# MCU_STM32F103RCT6.net
KiCad netlist of a schematic drawn in Altium Designer
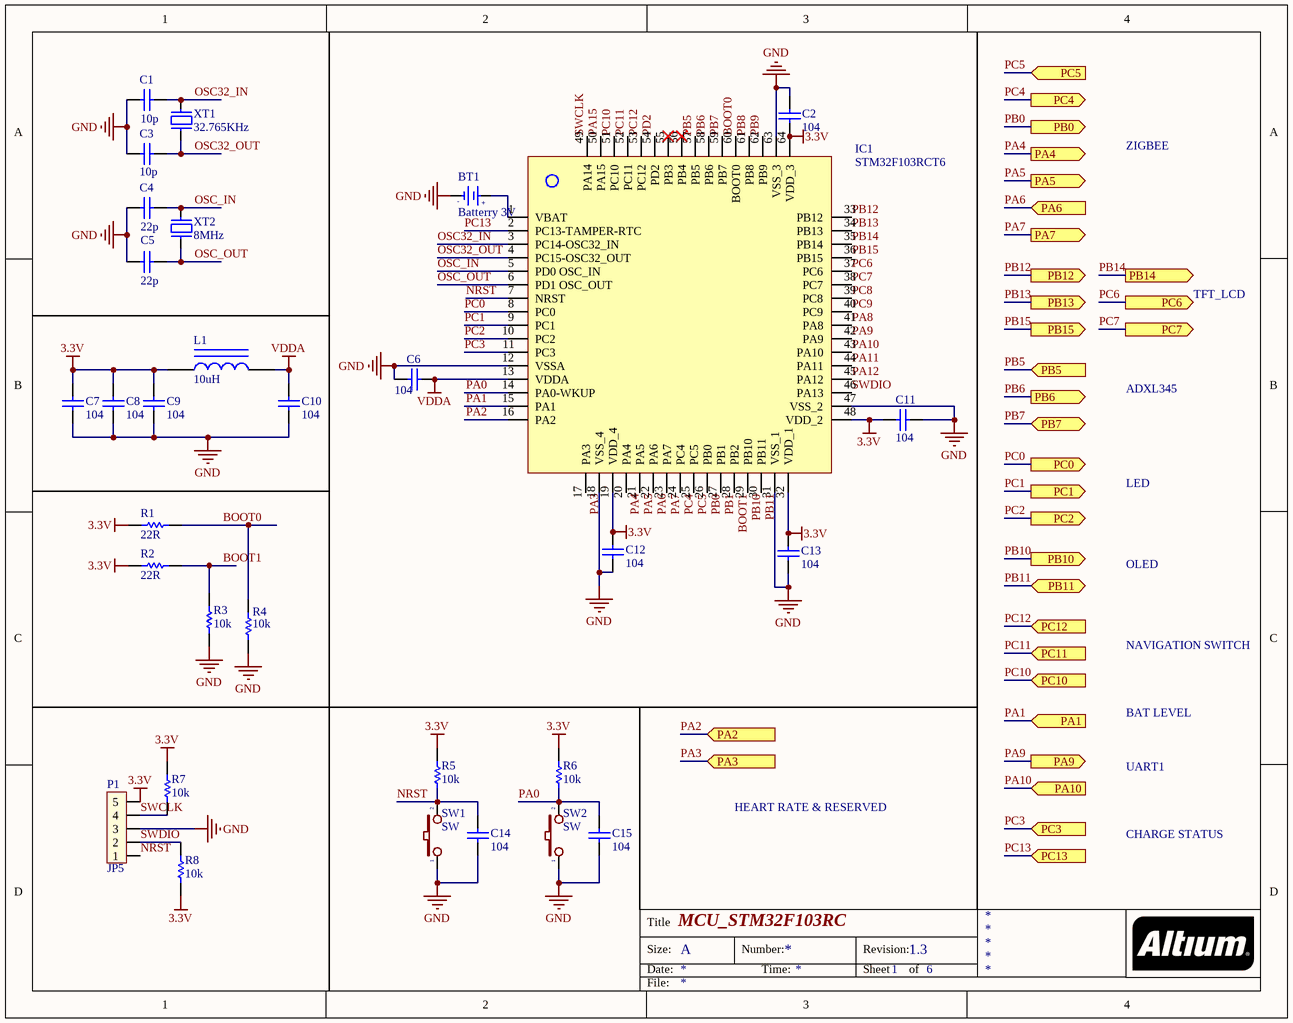
[diagram p0: MCU_STM32F103RCT6.SchDoc]

(export (version "E")
  (design (tool "Eeschema 10.0.6"))
  (components
    (comp (ref "BT1")
      (value "Batterry 3V")
      (footprint "Battery3V_SMD")
      (libsource (lib "HoangViet_AltiumLib") (part "Battery3V"))
    )
    (comp (ref "C1")
      (value "10p")
      (footprint "Cap 0805")
      (libsource (lib "HoangViet_AltiumLib") (part "Cap_0805"))
    )
    (comp (ref "C2")
      (value "104")
      (footprint "Cap 0805")
      (libsource (lib "HoangViet_AltiumLib") (part "Cap_0805"))
    )
    (comp (ref "C3")
      (value "10p")
      (footprint "Cap 0805")
      (libsource (lib "HoangViet_AltiumLib") (part "Cap_0805"))
    )
    (comp (ref "C4")
      (value "22p")
      (footprint "Cap 0805")
      (libsource (lib "HoangViet_AltiumLib") (part "Cap_0805"))
    )
    (comp (ref "C5")
      (value "22p")
      (footprint "Cap 0805")
      (libsource (lib "HoangViet_AltiumLib") (part "Cap_0805"))
    )
    (comp (ref "C6")
      (value "104")
      (footprint "Cap 0805")
      (libsource (lib "HoangViet_AltiumLib") (part "Cap_0805"))
    )
    (comp (ref "C7")
      (value "104")
      (footprint "Cap 0805")
      (libsource (lib "HoangViet_AltiumLib") (part "Cap_0805"))
    )
    (comp (ref "C8")
      (value "104")
      (footprint "Cap 0805")
      (libsource (lib "HoangViet_AltiumLib") (part "Cap_0805"))
    )
    (comp (ref "C9")
      (value "104")
      (footprint "Cap 0805")
      (libsource (lib "HoangViet_AltiumLib") (part "Cap_0805"))
    )
    (comp (ref "C10")
      (value "104")
      (footprint "Cap 0805")
      (libsource (lib "HoangViet_AltiumLib") (part "Cap_0805"))
    )
    (comp (ref "C11")
      (value "104")
      (footprint "Cap 0805")
      (libsource (lib "HoangViet_AltiumLib") (part "Cap_0805"))
    )
    (comp (ref "C12")
      (value "104")
      (footprint "Cap 0805")
      (libsource (lib "HoangViet_AltiumLib") (part "Cap_0805"))
    )
    (comp (ref "C13")
      (value "104")
      (footprint "Cap 0805")
      (libsource (lib "HoangViet_AltiumLib") (part "Cap_0805"))
    )
    (comp (ref "C14")
      (value "104")
      (footprint "Cap 0805")
      (libsource (lib "HoangViet_AltiumLib") (part "Cap_0805"))
    )
    (comp (ref "C15")
      (value "104")
      (footprint "Cap 0805")
      (libsource (lib "HoangViet_AltiumLib") (part "Cap_0805"))
    )
    (comp (ref "IC1")
      (value "STM32F103RCT6")
      (footprint "stm32f103rct6")
      (libsource (lib "linhien69") (part "stm32f103rct6"))
    )
    (comp (ref "L1")
      (value "10uH")
      (footprint "Inductor 0805")
      (description "inductor 0805")
      (libsource (lib "HoangViet_AltiumLib") (part "inductor_0805"))
    )
    (comp (ref "P1") (value "JP5") (footprint "JP5") (libsource (lib "linhien69") (part "JP5")))
    (comp (ref "R1")
      (value "22R")
      (footprint "RES 0805")
      (description "resistor smd0805")
      (libsource (lib "HoangViet_AltiumLib") (part "Res_0805"))
    )
    (comp (ref "R2")
      (value "22R")
      (footprint "RES 0805")
      (description "resistor smd0805")
      (libsource (lib "HoangViet_AltiumLib") (part "Res_0805"))
    )
    (comp (ref "R3")
      (value "10k")
      (footprint "RES 0805")
      (description "resistor smd0805")
      (libsource (lib "HoangViet_AltiumLib") (part "Res_0805"))
    )
    (comp (ref "R4")
      (value "10k")
      (footprint "RES 0805")
      (description "resistor smd0805")
      (libsource (lib "HoangViet_AltiumLib") (part "Res_0805"))
    )
    (comp (ref "R5")
      (value "10k")
      (footprint "RES 0805")
      (description "resistor smd0805")
      (libsource (lib "HoangViet_AltiumLib") (part "Res_0805"))
    )
    (comp (ref "R6")
      (value "10k")
      (footprint "RES 0805")
      (description "resistor smd0805")
      (libsource (lib "HoangViet_AltiumLib") (part "Res_0805"))
    )
    (comp (ref "R7")
      (value "10k")
      (footprint "RES 0805")
      (description "resistor smd0805")
      (libsource (lib "HoangViet_AltiumLib") (part "Res_0805"))
    )
    (comp (ref "R8")
      (value "10k")
      (footprint "RES 0805")
      (description "resistor smd0805")
      (libsource (lib "HoangViet_AltiumLib") (part "Res_0805"))
    )
    (comp (ref "SW1")
      (value "SW")
      (footprint "sw_ran_2pin")
      (description "Switch button 2 pin")
      (libsource (lib "linhien69") (part "SW2"))
    )
    (comp (ref "SW2")
      (value "SW")
      (footprint "sw_ran_2pin")
      (description "Switch button 2 pin")
      (libsource (lib "linhien69") (part "SW2"))
    )
    (comp (ref "XT1")
      (value "32.765KHz")
      (footprint "XTAL_32K")
      (description "Xtal")
      (libsource (lib "HoangViet_AltiumLib") (part "Xtal"))
    )
    (comp (ref "XT2")
      (value "8MHz")
      (footprint "XTAL_6035")
      (description "Xtal")
      (libsource (lib "HoangViet_AltiumLib") (part "Xtal"))
    )
  )
  (nets
    (net (code "1") (name "/BOOT0") (class "Default")
      (node (ref "IC1") (pin "60") (pinfunction "BOOT0_60") (pintype "passive"))
      (node (ref "R1") (pin "1") (pinfunction "1_1") (pintype "passive"))
      (node (ref "R4") (pin "2") (pinfunction "2_2") (pintype "passive"))
    )
    (net (code "2") (name "/BOOT1") (class "Default")
      (node (ref "IC1") (pin "28") (pinfunction "PB2_28") (pintype "passive"))
      (node (ref "R2") (pin "1") (pinfunction "1_1") (pintype "passive"))
      (node (ref "R3") (pin "2") (pinfunction "2_2") (pintype "passive"))
    )
    (net (code "3") (name "/NRST") (class "Default")
      (node (ref "C14") (pin "2") (pinfunction "2_2") (pintype "passive"))
      (node (ref "IC1") (pin "7") (pinfunction "NRST_7") (pintype "passive"))
      (node (ref "P1") (pin "1") (pinfunction "1_1") (pintype "passive"))
      (node (ref "R5") (pin "1") (pinfunction "1_1") (pintype "passive"))
      (node (ref "SW1") (pin "2") (pinfunction "2_2") (pintype "passive"))
    )
    (net (code "4") (name "/OSC32_IN") (class "Default")
      (node (ref "C1") (pin "1") (pinfunction "1_1") (pintype "passive"))
      (node (ref "IC1") (pin "3") (pinfunction "PC14-OSC32_IN_3") (pintype "passive"))
      (node (ref "XT1") (pin "2") (pinfunction "2_2") (pintype "passive"))
    )
    (net (code "5") (name "/OSC32_OUT") (class "Default")
      (node (ref "C3") (pin "1") (pinfunction "1_1") (pintype "passive"))
      (node (ref "IC1") (pin "4") (pinfunction "PC15-OSC32_OUT_4") (pintype "passive"))
      (node (ref "XT1") (pin "1") (pinfunction "1_1") (pintype "passive"))
    )
    (net (code "6") (name "/OSC_IN") (class "Default")
      (node (ref "C4") (pin "1") (pinfunction "1_1") (pintype "passive"))
      (node (ref "IC1") (pin "5") (pinfunction "PD0_OSC_IN_5") (pintype "passive"))
      (node (ref "XT2") (pin "2") (pinfunction "2_2") (pintype "passive"))
    )
    (net (code "7") (name "/OSC_OUT") (class "Default")
      (node (ref "C5") (pin "1") (pinfunction "1_1") (pintype "passive"))
      (node (ref "IC1") (pin "6") (pinfunction "PD1_OSC_OUT_6") (pintype "passive"))
      (node (ref "XT2") (pin "1") (pinfunction "1_1") (pintype "passive"))
    )
    (net (code "8") (name "/PA0") (class "Default")
      (node (ref "C15") (pin "2") (pinfunction "2_2") (pintype "passive"))
      (node (ref "IC1") (pin "14") (pinfunction "PA0-WKUP_14") (pintype "passive"))
      (node (ref "R6") (pin "1") (pinfunction "1_1") (pintype "passive"))
      (node (ref "SW2") (pin "2") (pinfunction "2_2") (pintype "passive"))
    )
    (net (code "9") (name "/PA1") (class "Default")
      (node (ref "IC1") (pin "15") (pinfunction "PA1_15") (pintype "passive"))
    )
    (net (code "10") (name "/PA2") (class "Default")
      (node (ref "IC1") (pin "16") (pinfunction "PA2_16") (pintype "passive"))
    )
    (net (code "11") (name "/PA3") (class "Default")
      (node (ref "IC1") (pin "17") (pinfunction "PA3_17") (pintype "passive"))
    )
    (net (code "12") (name "/PA4") (class "Default")
      (node (ref "IC1") (pin "20") (pinfunction "PA4_20") (pintype "passive"))
    )
    (net (code "13") (name "/PA5") (class "Default")
      (node (ref "IC1") (pin "21") (pinfunction "PA5_21") (pintype "passive"))
    )
    (net (code "14") (name "/PA6") (class "Default")
      (node (ref "IC1") (pin "22") (pinfunction "PA6_22") (pintype "passive"))
    )
    (net (code "15") (name "/PA7") (class "Default")
      (node (ref "IC1") (pin "23") (pinfunction "PA7_23") (pintype "passive"))
    )
    (net (code "16") (name "/PA8") (class "Default")
      (node (ref "IC1") (pin "41") (pinfunction "PA8_41") (pintype "passive"))
    )
    (net (code "17") (name "/PA9") (class "Default")
      (node (ref "IC1") (pin "42") (pinfunction "PA9_42") (pintype "passive"))
    )
    (net (code "18") (name "/PA10") (class "Default")
      (node (ref "IC1") (pin "43") (pinfunction "PA10_43") (pintype "passive"))
    )
    (net (code "19") (name "/PA11") (class "Default")
      (node (ref "IC1") (pin "44") (pinfunction "PA11_44") (pintype "passive"))
    )
    (net (code "20") (name "/PA12") (class "Default")
      (node (ref "IC1") (pin "45") (pinfunction "PA12_45") (pintype "passive"))
    )
    (net (code "21") (name "/PA15") (class "Default")
      (node (ref "IC1") (pin "50") (pinfunction "PA15_50") (pintype "passive"))
    )
    (net (code "22") (name "/PB0") (class "Default")
      (node (ref "IC1") (pin "26") (pinfunction "PB0_26") (pintype "passive"))
    )
    (net (code "23") (name "/PB1") (class "Default")
      (node (ref "IC1") (pin "27") (pinfunction "PB1_27") (pintype "passive"))
    )
    (net (code "24") (name "/PB5") (class "Default")
      (node (ref "IC1") (pin "57") (pinfunction "PB5_57") (pintype "passive"))
    )
    (net (code "25") (name "/PB6") (class "Default")
      (node (ref "IC1") (pin "58") (pinfunction "PB6_58") (pintype "passive"))
    )
    (net (code "26") (name "/PB7") (class "Default")
      (node (ref "IC1") (pin "59") (pinfunction "PB7_59") (pintype "passive"))
    )
    (net (code "27") (name "/PB8") (class "Default")
      (node (ref "IC1") (pin "61") (pinfunction "PB8_61") (pintype "passive"))
    )
    (net (code "28") (name "/PB9") (class "Default")
      (node (ref "IC1") (pin "62") (pinfunction "PB9_62") (pintype "passive"))
    )
    (net (code "29") (name "/PB10") (class "Default")
      (node (ref "IC1") (pin "29") (pinfunction "PB10_29") (pintype "passive"))
    )
    (net (code "30") (name "/PB11") (class "Default")
      (node (ref "IC1") (pin "30") (pinfunction "PB11_30") (pintype "passive"))
    )
    (net (code "31") (name "/PB12") (class "Default")
      (node (ref "IC1") (pin "33") (pinfunction "PB12_33") (pintype "passive"))
    )
    (net (code "32") (name "/PB13") (class "Default")
      (node (ref "IC1") (pin "34") (pinfunction "PB13_34") (pintype "passive"))
    )
    (net (code "33") (name "/PB14") (class "Default")
      (node (ref "IC1") (pin "35") (pinfunction "PB14_35") (pintype "passive"))
    )
    (net (code "34") (name "/PB15") (class "Default")
      (node (ref "IC1") (pin "36") (pinfunction "PB15_36") (pintype "passive"))
    )
    (net (code "35") (name "/PC0") (class "Default")
      (node (ref "IC1") (pin "8") (pinfunction "PC0_8") (pintype "passive"))
    )
    (net (code "36") (name "/PC1") (class "Default")
      (node (ref "IC1") (pin "9") (pinfunction "PC1_9") (pintype "passive"))
    )
    (net (code "37") (name "/PC2") (class "Default")
      (node (ref "IC1") (pin "10") (pinfunction "PC2_10") (pintype "passive"))
    )
    (net (code "38") (name "/PC3") (class "Default")
      (node (ref "IC1") (pin "11") (pinfunction "PC3_11") (pintype "passive"))
    )
    (net (code "39") (name "/PC4") (class "Default")
      (node (ref "IC1") (pin "24") (pinfunction "PC4_24") (pintype "passive"))
    )
    (net (code "40") (name "/PC5") (class "Default")
      (node (ref "IC1") (pin "25") (pinfunction "PC5_25") (pintype "passive"))
    )
    (net (code "41") (name "/PC6") (class "Default")
      (node (ref "IC1") (pin "37") (pinfunction "PC6_37") (pintype "passive"))
    )
    (net (code "42") (name "/PC7") (class "Default")
      (node (ref "IC1") (pin "38") (pinfunction "PC7_38") (pintype "passive"))
    )
    (net (code "43") (name "/PC8") (class "Default")
      (node (ref "IC1") (pin "39") (pinfunction "PC8_39") (pintype "passive"))
    )
    (net (code "44") (name "/PC9") (class "Default")
      (node (ref "IC1") (pin "40") (pinfunction "PC9_40") (pintype "passive"))
    )
    (net (code "45") (name "/PC10") (class "Default")
      (node (ref "IC1") (pin "51") (pinfunction "PC10_51") (pintype "passive"))
    )
    (net (code "46") (name "/PC11") (class "Default")
      (node (ref "IC1") (pin "52") (pinfunction "PC11_52") (pintype "passive"))
    )
    (net (code "47") (name "/PC12") (class "Default")
      (node (ref "IC1") (pin "53") (pinfunction "PC12_53") (pintype "passive"))
    )
    (net (code "48") (name "/PC13") (class "Default")
      (node (ref "IC1") (pin "2") (pinfunction "PC13-TAMPER-RTC_2") (pintype "passive"))
    )
    (net (code "49") (name "/PD2") (class "Default")
      (node (ref "IC1") (pin "54") (pinfunction "PD2_54") (pintype "passive"))
    )
    (net (code "50") (name "/SWCLK") (class "Default")
      (node (ref "IC1") (pin "49") (pinfunction "PA14_49") (pintype "passive"))
      (node (ref "P1") (pin "4") (pinfunction "4_4") (pintype "passive"))
      (node (ref "R7") (pin "1") (pinfunction "1_1") (pintype "passive"))
    )
    (net (code "51") (name "/SWDIO") (class "Default")
      (node (ref "IC1") (pin "46") (pinfunction "PA13_46") (pintype "passive"))
      (node (ref "P1") (pin "2") (pinfunction "2_2") (pintype "passive"))
      (node (ref "R8") (pin "2") (pinfunction "2_2") (pintype "passive"))
    )
    (net (code "52") (name "3.3V") (class "Default")
      (node (ref "C11") (pin "2") (pinfunction "2_2") (pintype "passive"))
      (node (ref "C12") (pin "2") (pinfunction "2_2") (pintype "passive"))
      (node (ref "C13") (pin "2") (pinfunction "2_2") (pintype "passive"))
      (node (ref "C2") (pin "2") (pinfunction "2_2") (pintype "passive"))
      (node (ref "C7") (pin "2") (pinfunction "2_2") (pintype "passive"))
      (node (ref "C8") (pin "2") (pinfunction "2_2") (pintype "passive"))
      (node (ref "C9") (pin "2") (pinfunction "2_2") (pintype "passive"))
      (node (ref "IC1") (pin "19") (pinfunction "VDD_4_19") (pintype "passive"))
      (node (ref "IC1") (pin "32") (pinfunction "VDD_1_32") (pintype "passive"))
      (node (ref "IC1") (pin "48") (pinfunction "VDD_2_48") (pintype "passive"))
      (node (ref "IC1") (pin "64") (pinfunction "VDD_3_64") (pintype "passive"))
      (node (ref "L1") (pin "1") (pinfunction "1_1") (pintype "passive"))
      (node (ref "P1") (pin "5") (pinfunction "5_5") (pintype "passive"))
      (node (ref "R1") (pin "2") (pinfunction "2_2") (pintype "passive"))
      (node (ref "R2") (pin "2") (pinfunction "2_2") (pintype "passive"))
      (node (ref "R5") (pin "2") (pinfunction "2_2") (pintype "passive"))
      (node (ref "R6") (pin "2") (pinfunction "2_2") (pintype "passive"))
      (node (ref "R7") (pin "2") (pinfunction "2_2") (pintype "passive"))
      (node (ref "R8") (pin "1") (pinfunction "1_1") (pintype "passive"))
    )
    (net (code "53") (name "GND") (class "Default")
      (node (ref "BT1") (pin "2") (pinfunction "GND_2") (pintype "passive"))
      (node (ref "C1") (pin "2") (pinfunction "2_2") (pintype "passive"))
      (node (ref "C10") (pin "1") (pinfunction "1_1") (pintype "passive"))
      (node (ref "C11") (pin "1") (pinfunction "1_1") (pintype "passive"))
      (node (ref "C12") (pin "1") (pinfunction "1_1") (pintype "passive"))
      (node (ref "C13") (pin "1") (pinfunction "1_1") (pintype "passive"))
      (node (ref "C14") (pin "1") (pinfunction "1_1") (pintype "passive"))
      (node (ref "C15") (pin "1") (pinfunction "1_1") (pintype "passive"))
      (node (ref "C2") (pin "1") (pinfunction "1_1") (pintype "passive"))
      (node (ref "C3") (pin "2") (pinfunction "2_2") (pintype "passive"))
      (node (ref "C4") (pin "2") (pinfunction "2_2") (pintype "passive"))
      (node (ref "C5") (pin "2") (pinfunction "2_2") (pintype "passive"))
      (node (ref "C6") (pin "2") (pinfunction "2_2") (pintype "passive"))
      (node (ref "C7") (pin "1") (pinfunction "1_1") (pintype "passive"))
      (node (ref "C8") (pin "1") (pinfunction "1_1") (pintype "passive"))
      (node (ref "C9") (pin "1") (pinfunction "1_1") (pintype "passive"))
      (node (ref "IC1") (pin "12") (pinfunction "VSSA_12") (pintype "passive"))
      (node (ref "IC1") (pin "18") (pinfunction "VSS_4_18") (pintype "passive"))
      (node (ref "IC1") (pin "31") (pinfunction "VSS_1_31") (pintype "passive"))
      (node (ref "IC1") (pin "47") (pinfunction "VSS_2_47") (pintype "passive"))
      (node (ref "IC1") (pin "63") (pinfunction "VSS_3_63") (pintype "passive"))
      (node (ref "P1") (pin "3") (pinfunction "3_3") (pintype "passive"))
      (node (ref "R3") (pin "1") (pinfunction "1_1") (pintype "passive"))
      (node (ref "R4") (pin "1") (pinfunction "1_1") (pintype "passive"))
      (node (ref "SW1") (pin "1") (pinfunction "1_1") (pintype "passive"))
      (node (ref "SW2") (pin "1") (pinfunction "1_1") (pintype "passive"))
    )
    (net (code "54") (name "Net-(BT1-+3V)") (class "Default")
      (node (ref "BT1") (pin "1") (pinfunction "+3V_1") (pintype "passive"))
      (node (ref "IC1") (pin "1") (pinfunction "VBAT_1") (pintype "passive"))
    )
    (net (code "55") (name "VDDA") (class "Default")
      (node (ref "C10") (pin "2") (pinfunction "2_2") (pintype "passive"))
      (node (ref "C6") (pin "1") (pinfunction "1_1") (pintype "passive"))
      (node (ref "IC1") (pin "13") (pinfunction "VDDA_13") (pintype "passive"))
      (node (ref "L1") (pin "2") (pinfunction "2_2") (pintype "passive"))
    )
    (net (code "56") (name "unconnected-(IC1-PB3-Pad55)") (class "Default")
      (node (ref "IC1") (pin "55") (pinfunction "PB3_55") (pintype "passive+no_connect"))
    )
    (net (code "57") (name "unconnected-(IC1-PB4-Pad56)") (class "Default")
      (node (ref "IC1") (pin "56") (pinfunction "PB4_56") (pintype "passive+no_connect"))
    )
  )
)
